# pendant.net
KiCad netlist of a schematic drawn in EAGLE
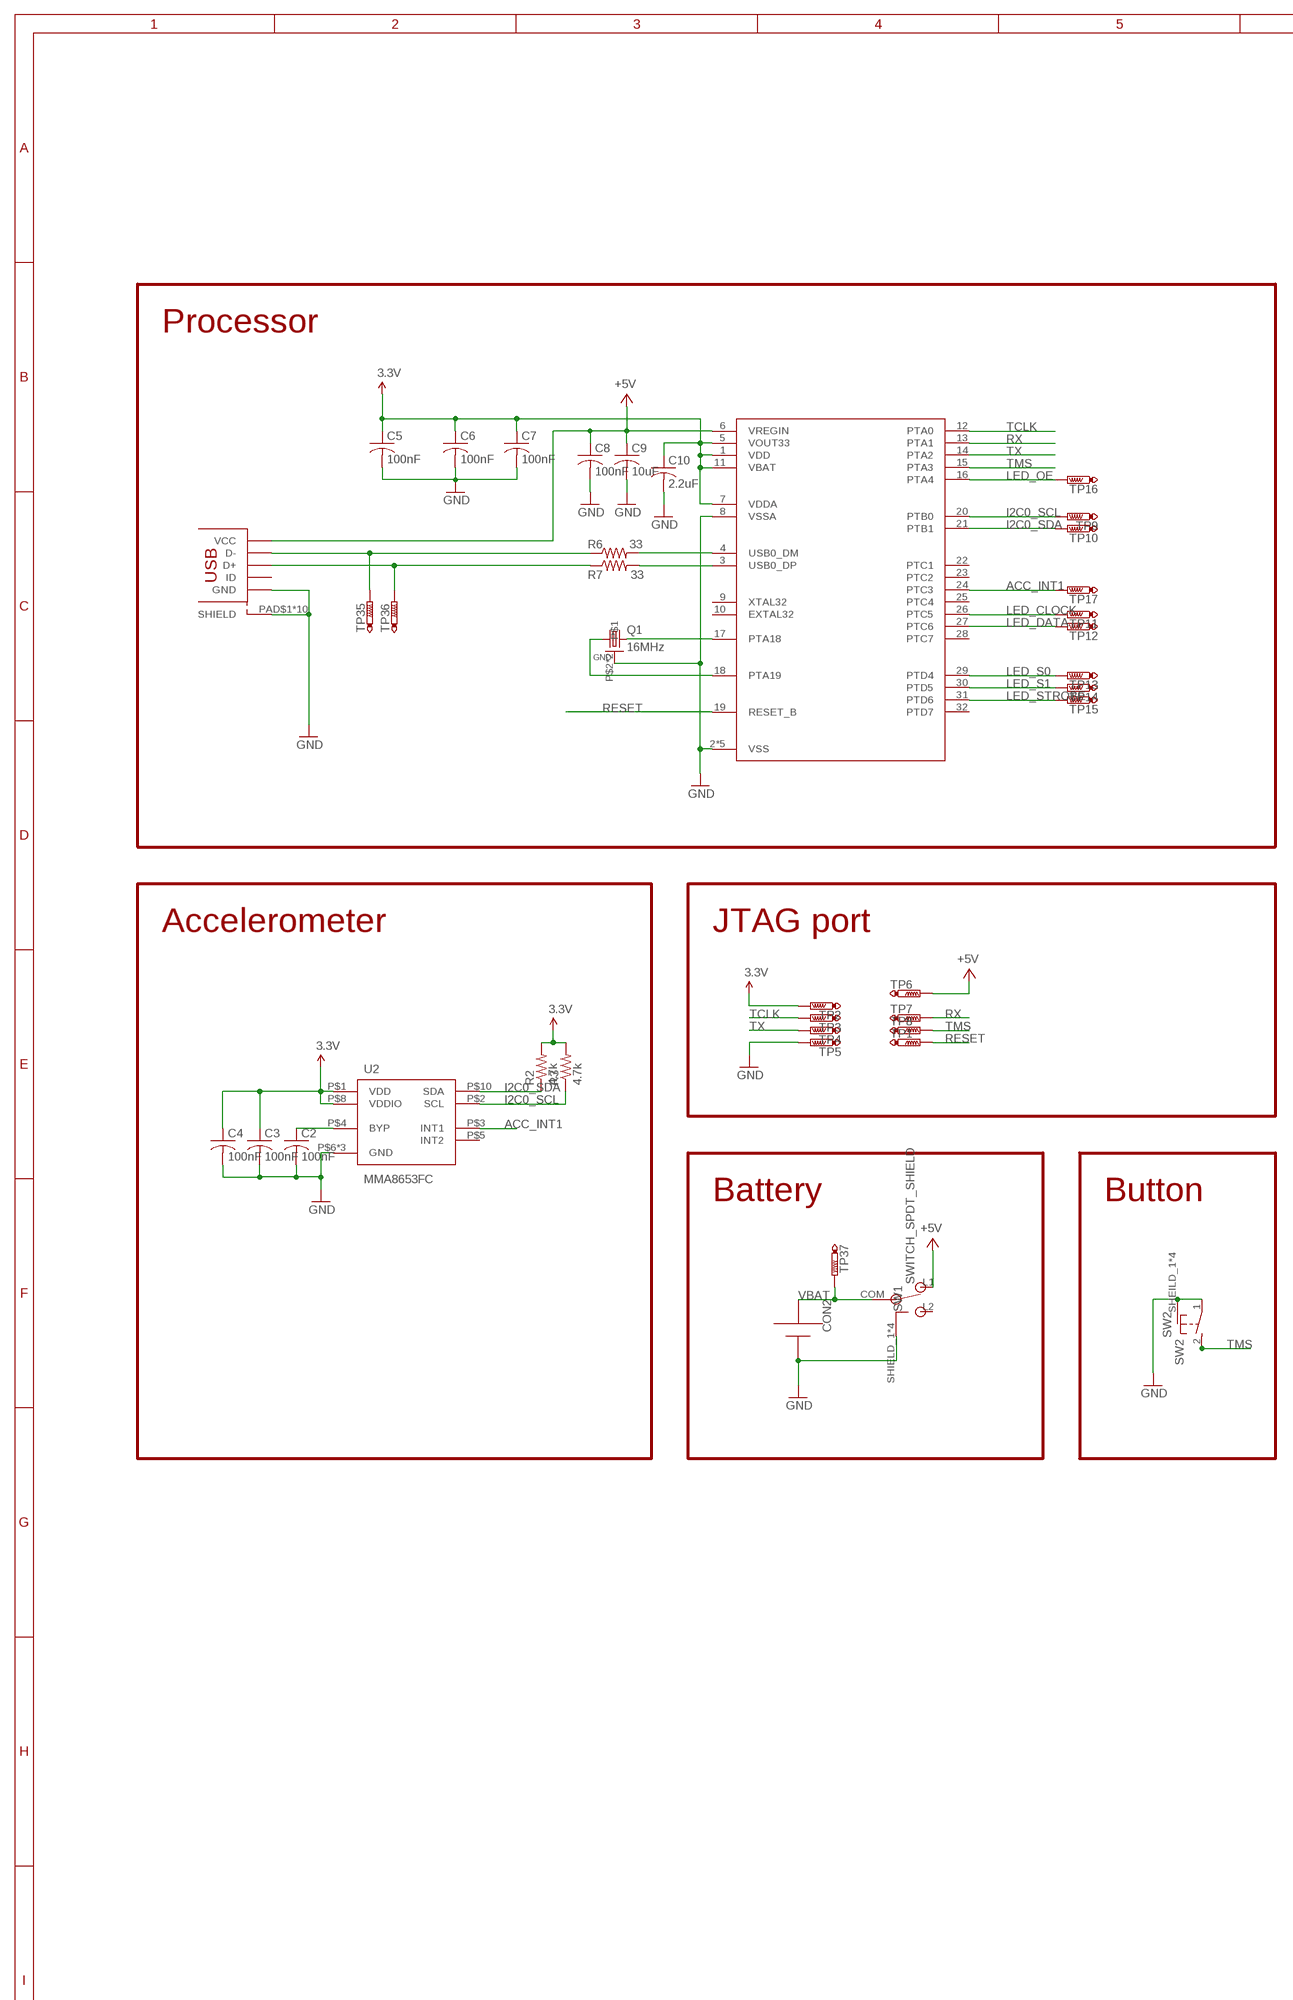
[diagram p0: schematic, sheet 1, part 1 of 2]
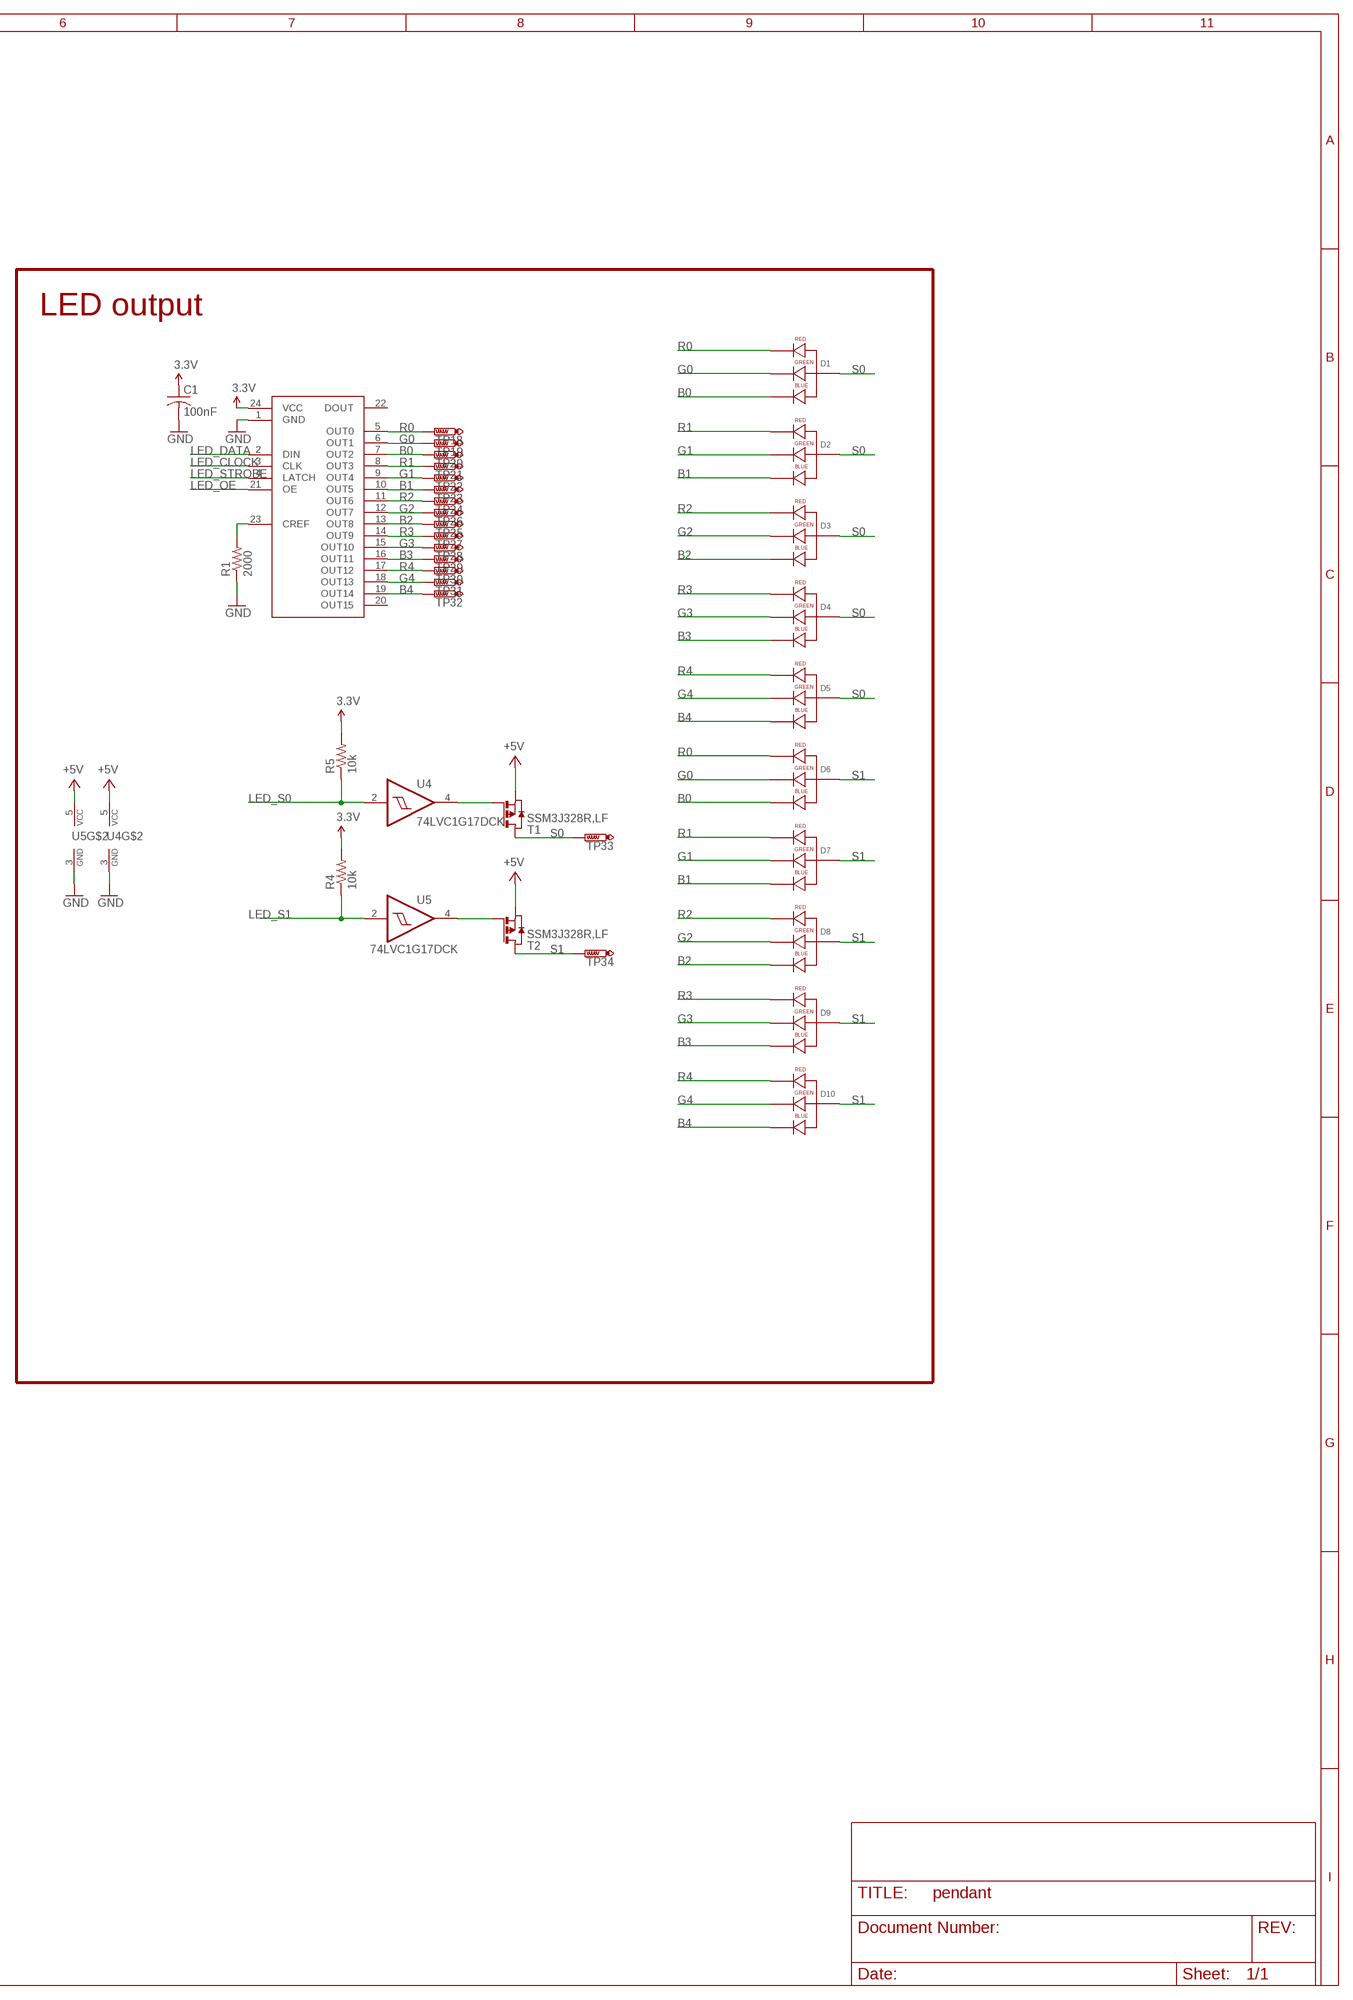
[diagram p1: schematic, sheet 1, part 2 of 2]

(export (version "E")
  (design (tool "Eeschema 10.0.6"))
  (components
    (comp (ref "C1")
      (value "100nF")
      (footprint "eagle-import:C0402")
      (libsource (lib "eagle-import") (part "C-USC0402"))
    )
    (comp (ref "C2")
      (value "100nF")
      (footprint "eagle-import:C0402")
      (libsource (lib "eagle-import") (part "C-USC0402"))
    )
    (comp (ref "C3")
      (value "100nF")
      (footprint "eagle-import:C0402")
      (libsource (lib "eagle-import") (part "C-USC0402"))
    )
    (comp (ref "C4")
      (value "100nF")
      (footprint "eagle-import:C0402")
      (libsource (lib "eagle-import") (part "C-USC0402"))
    )
    (comp (ref "C5")
      (value "100nF")
      (footprint "eagle-import:C0402")
      (libsource (lib "eagle-import") (part "C-USC0402"))
    )
    (comp (ref "C6")
      (value "100nF")
      (footprint "eagle-import:C0402")
      (libsource (lib "eagle-import") (part "C-USC0402"))
    )
    (comp (ref "C7")
      (value "100nF")
      (footprint "eagle-import:C0402")
      (libsource (lib "eagle-import") (part "C-USC0402"))
    )
    (comp (ref "C8")
      (value "100nF")
      (footprint "eagle-import:C0402")
      (libsource (lib "eagle-import") (part "C-USC0402"))
    )
    (comp (ref "C9")
      (value "10uF")
      (footprint "eagle-import:C0603")
      (libsource (lib "eagle-import") (part "C-USC0603"))
    )
    (comp (ref "C10")
      (value "2.2uF")
      (footprint "eagle-import:C0402")
      (libsource (lib "eagle-import") (part "C-USC0402"))
    )
    (comp (ref "CON1")
      (value "USB_MICROSMT+THRUHULE")
      (footprint "eagle-import:USB_MICRO_THRUHOLE")
      (libsource (lib "eagle-import") (part "USB_MICROSMT+THRUHULE"))
    )
    (comp (ref "CON2")
      (value "CR2032X2")
      (footprint "eagle-import:CR2032X2")
      (libsource (lib "eagle-import") (part "CR2032X2"))
    )
    (comp (ref "D1")
      (value "LED-RGB5050")
      (footprint "eagle-import:LED-TRICOLOR-5050-FIXED")
      (libsource (lib "eagle-import") (part "LED-RGB5050"))
    )
    (comp (ref "D2")
      (value "LED-RGB5050")
      (footprint "eagle-import:LED-TRICOLOR-5050-FIXED")
      (libsource (lib "eagle-import") (part "LED-RGB5050"))
    )
    (comp (ref "D3")
      (value "LED-RGB5050")
      (footprint "eagle-import:LED-TRICOLOR-5050-FIXED")
      (libsource (lib "eagle-import") (part "LED-RGB5050"))
    )
    (comp (ref "D4")
      (value "LED-RGB5050")
      (footprint "eagle-import:LED-TRICOLOR-5050-FIXED")
      (libsource (lib "eagle-import") (part "LED-RGB5050"))
    )
    (comp (ref "D5")
      (value "LED-RGB5050")
      (footprint "eagle-import:LED-TRICOLOR-5050-FIXED")
      (libsource (lib "eagle-import") (part "LED-RGB5050"))
    )
    (comp (ref "D6")
      (value "LED-RGB5050")
      (footprint "eagle-import:LED-TRICOLOR-5050-FIXED")
      (libsource (lib "eagle-import") (part "LED-RGB5050"))
    )
    (comp (ref "D7")
      (value "LED-RGB5050")
      (footprint "eagle-import:LED-TRICOLOR-5050-FIXED")
      (libsource (lib "eagle-import") (part "LED-RGB5050"))
    )
    (comp (ref "D8")
      (value "LED-RGB5050")
      (footprint "eagle-import:LED-TRICOLOR-5050-FIXED")
      (libsource (lib "eagle-import") (part "LED-RGB5050"))
    )
    (comp (ref "D9")
      (value "LED-RGB5050")
      (footprint "eagle-import:LED-TRICOLOR-5050-FIXED")
      (libsource (lib "eagle-import") (part "LED-RGB5050"))
    )
    (comp (ref "D10")
      (value "LED-RGB5050")
      (footprint "eagle-import:LED-TRICOLOR-5050-FIXED")
      (libsource (lib "eagle-import") (part "LED-RGB5050"))
    )
    (comp (ref "Q1")
      (value "16MHz")
      (footprint "eagle-import:CRYSTAL_3225")
      (libsource (lib "eagle-import") (part "CRYSTAL_4PAD"))
    )
    (comp (ref "R1")
      (value "2000")
      (footprint "eagle-import:R0402")
      (libsource (lib "eagle-import") (part "R-US_R0402"))
    )
    (comp (ref "R2")
      (value "4.7k")
      (footprint "eagle-import:R0402")
      (libsource (lib "eagle-import") (part "R-US_R0402"))
    )
    (comp (ref "R3")
      (value "4.7k")
      (footprint "eagle-import:R0402")
      (libsource (lib "eagle-import") (part "R-US_R0402"))
    )
    (comp (ref "R4")
      (value "10k")
      (footprint "eagle-import:R0402")
      (libsource (lib "eagle-import") (part "R-US_R0402"))
    )
    (comp (ref "R5")
      (value "10k")
      (footprint "eagle-import:R0402")
      (libsource (lib "eagle-import") (part "R-US_R0402"))
    )
    (comp (ref "R6")
      (value "33")
      (footprint "eagle-import:R0402")
      (libsource (lib "eagle-import") (part "R-US_R0402"))
    )
    (comp (ref "R7")
      (value "33")
      (footprint "eagle-import:R0402")
      (libsource (lib "eagle-import") (part "R-US_R0402"))
    )
    (comp (ref "SW1")
      (value "SWITCH_SPDT_SHIELD")
      (footprint "eagle-import:SWITCH_SMD_90_DEGREE")
      (libsource (lib "eagle-import") (part "SWITCH_SPDT_SHIELD"))
    )
    (comp (ref "SW2")
      (value "SW2")
      (footprint "eagle-import:BUTTON_MOMENTARY_MP5")
      (libsource (lib "eagle-import") (part "BUTTON_MOMENTARY_GROUND"))
    )
    (comp (ref "T1")
      (value "SSM3J328R,LF")
      (footprint "eagle-import:SOT-23")
      (libsource (lib "eagle-import") (part "PMOSSOT23"))
    )
    (comp (ref "T2")
      (value "SSM3J328R,LF")
      (footprint "eagle-import:SOT-23")
      (libsource (lib "eagle-import") (part "PMOSSOT23"))
    )
    (comp (ref "TP1")
      (value "PTR1B1,27")
      (footprint "eagle-import:B1,27")
      (libsource (lib "eagle-import") (part "PTR1B1,27"))
    )
    (comp (ref "TP2")
      (value "PTR1B1,27")
      (footprint "eagle-import:B1,27")
      (libsource (lib "eagle-import") (part "PTR1B1,27"))
    )
    (comp (ref "TP3")
      (value "PTR1B1,27")
      (footprint "eagle-import:B1,27")
      (libsource (lib "eagle-import") (part "PTR1B1,27"))
    )
    (comp (ref "TP4")
      (value "PTR1B1,27")
      (footprint "eagle-import:B1,27")
      (libsource (lib "eagle-import") (part "PTR1B1,27"))
    )
    (comp (ref "TP5")
      (value "PTR1B1,27")
      (footprint "eagle-import:B1,27")
      (libsource (lib "eagle-import") (part "PTR1B1,27"))
    )
    (comp (ref "TP6")
      (value "PTR1B1,27")
      (footprint "eagle-import:B1,27")
      (libsource (lib "eagle-import") (part "PTR1B1,27"))
    )
    (comp (ref "TP7")
      (value "PTR1B1,27")
      (footprint "eagle-import:B1,27")
      (libsource (lib "eagle-import") (part "PTR1B1,27"))
    )
    (comp (ref "TP8")
      (value "PTR1B1,27")
      (footprint "eagle-import:B1,27")
      (libsource (lib "eagle-import") (part "PTR1B1,27"))
    )
    (comp (ref "TP9")
      (value "PTR1B1,27")
      (footprint "eagle-import:B1,27")
      (libsource (lib "eagle-import") (part "PTR1B1,27"))
    )
    (comp (ref "TP10")
      (value "PTR1B1,27")
      (footprint "eagle-import:B1,27")
      (libsource (lib "eagle-import") (part "PTR1B1,27"))
    )
    (comp (ref "TP11")
      (value "PTR1B1,27")
      (footprint "eagle-import:B1,27")
      (libsource (lib "eagle-import") (part "PTR1B1,27"))
    )
    (comp (ref "TP12")
      (value "PTR1B1,27")
      (footprint "eagle-import:B1,27")
      (libsource (lib "eagle-import") (part "PTR1B1,27"))
    )
    (comp (ref "TP13")
      (value "PTR1B1,27")
      (footprint "eagle-import:B1,27")
      (libsource (lib "eagle-import") (part "PTR1B1,27"))
    )
    (comp (ref "TP14")
      (value "PTR1B1,27")
      (footprint "eagle-import:B1,27")
      (libsource (lib "eagle-import") (part "PTR1B1,27"))
    )
    (comp (ref "TP15")
      (value "PTR1B1,27")
      (footprint "eagle-import:B1,27")
      (libsource (lib "eagle-import") (part "PTR1B1,27"))
    )
    (comp (ref "TP16")
      (value "PTR1B1,27")
      (footprint "eagle-import:B1,27")
      (libsource (lib "eagle-import") (part "PTR1B1,27"))
    )
    (comp (ref "TP17")
      (value "PTR1B1,27")
      (footprint "eagle-import:B1,27")
      (libsource (lib "eagle-import") (part "PTR1B1,27"))
    )
    (comp (ref "TP18")
      (value "PTR1B1,27")
      (footprint "eagle-import:B1,27")
      (libsource (lib "eagle-import") (part "PTR1B1,27"))
    )
    (comp (ref "TP19")
      (value "PTR1B1,27")
      (footprint "eagle-import:B1,27")
      (libsource (lib "eagle-import") (part "PTR1B1,27"))
    )
    (comp (ref "TP20")
      (value "PTR1B1,27")
      (footprint "eagle-import:B1,27")
      (libsource (lib "eagle-import") (part "PTR1B1,27"))
    )
    (comp (ref "TP21")
      (value "PTR1B1,27")
      (footprint "eagle-import:B1,27")
      (libsource (lib "eagle-import") (part "PTR1B1,27"))
    )
    (comp (ref "TP22")
      (value "PTR1B1,27")
      (footprint "eagle-import:B1,27")
      (libsource (lib "eagle-import") (part "PTR1B1,27"))
    )
    (comp (ref "TP23")
      (value "PTR1B1,27")
      (footprint "eagle-import:B1,27")
      (libsource (lib "eagle-import") (part "PTR1B1,27"))
    )
    (comp (ref "TP24")
      (value "PTR1B1,27")
      (footprint "eagle-import:B1,27")
      (libsource (lib "eagle-import") (part "PTR1B1,27"))
    )
    (comp (ref "TP25")
      (value "PTR1B1,27")
      (footprint "eagle-import:B1,27")
      (libsource (lib "eagle-import") (part "PTR1B1,27"))
    )
    (comp (ref "TP26")
      (value "PTR1B1,27")
      (footprint "eagle-import:B1,27")
      (libsource (lib "eagle-import") (part "PTR1B1,27"))
    )
    (comp (ref "TP27")
      (value "PTR1B1,27")
      (footprint "eagle-import:B1,27")
      (libsource (lib "eagle-import") (part "PTR1B1,27"))
    )
    (comp (ref "TP28")
      (value "PTR1B1,27")
      (footprint "eagle-import:B1,27")
      (libsource (lib "eagle-import") (part "PTR1B1,27"))
    )
    (comp (ref "TP29")
      (value "PTR1B1,27")
      (footprint "eagle-import:B1,27")
      (libsource (lib "eagle-import") (part "PTR1B1,27"))
    )
    (comp (ref "TP30")
      (value "PTR1B1,27")
      (footprint "eagle-import:B1,27")
      (libsource (lib "eagle-import") (part "PTR1B1,27"))
    )
    (comp (ref "TP31")
      (value "PTR1B1,27")
      (footprint "eagle-import:B1,27")
      (libsource (lib "eagle-import") (part "PTR1B1,27"))
    )
    (comp (ref "TP32")
      (value "PTR1B1,27")
      (footprint "eagle-import:B1,27")
      (libsource (lib "eagle-import") (part "PTR1B1,27"))
    )
    (comp (ref "TP33")
      (value "PTR1B1,27")
      (footprint "eagle-import:B1,27")
      (libsource (lib "eagle-import") (part "PTR1B1,27"))
    )
    (comp (ref "TP34")
      (value "PTR1B1,27")
      (footprint "eagle-import:B1,27")
      (libsource (lib "eagle-import") (part "PTR1B1,27"))
    )
    (comp (ref "TP35")
      (value "PTR1B1,27")
      (footprint "eagle-import:B1,27")
      (libsource (lib "eagle-import") (part "PTR1B1,27"))
    )
    (comp (ref "TP36")
      (value "PTR1B1,27")
      (footprint "eagle-import:B1,27")
      (libsource (lib "eagle-import") (part "PTR1B1,27"))
    )
    (comp (ref "TP37")
      (value "PTR1B1,27")
      (footprint "eagle-import:B1,27")
      (libsource (lib "eagle-import") (part "PTR1B1,27"))
    )
    (comp (ref "U1")
      (value "MK20D--VFM5")
      (footprint "eagle-import:QFN32_5X5_LONGLEADS")
      (libsource (lib "eagle-import") (part "MK20D--VFM5"))
    )
    (comp (ref "U2")
      (value "MMA8653FC")
      (footprint "eagle-import:VFDFN-10")
      (libsource (lib "eagle-import") (part "MMA8653FC"))
    )
    (comp (ref "U3")
      (value "ICN2026DF")
      (footprint "eagle-import:SMD-24-1MM")
      (libsource (lib "eagle-import") (part "ICN2026DF"))
    )
    (comp (ref "U4")
      (value "74LVC1G17DCK")
      (footprint "eagle-import:SC70-5")
      (libsource (lib "eagle-import") (part "741G17DCKLVC"))
    )
    (comp (ref "U5")
      (value "74LVC1G17DCK")
      (footprint "eagle-import:SC70-5")
      (libsource (lib "eagle-import") (part "741G17DCKLVC"))
    )
  )
  (nets
    (net (code "1") (name "+5V") (class "Default")
      (node (ref "C8") (pin "1") (pinfunction "1_1") (pintype "passive"))
      (node (ref "C9") (pin "1") (pinfunction "1_1") (pintype "passive"))
      (node (ref "CON1") (pin "PIN$1") (pinfunction "VCC_PIN$1") (pintype "bidirectional"))
      (node (ref "SW1") (pin "L1") (pinfunction "L1_L1") (pintype "passive"))
      (node (ref "T1") (pin "2") (pinfunction "S_2") (pintype "passive"))
      (node (ref "T2") (pin "2") (pinfunction "S_2") (pintype "passive"))
      (node (ref "TP6") (pin "TP") (pinfunction "TP_TP") (pintype "input"))
      (node (ref "U1") (pin "6") (pinfunction "VREGIN_6") (pintype "bidirectional"))
      (node (ref "U4") (pin "5") (pinfunction "VCC_5") (pintype "power_in"))
      (node (ref "U5") (pin "5") (pinfunction "VCC_5") (pintype "power_in"))
    )
    (net (code "2") (name "/ACC_INT1") (class "Default")
      (node (ref "TP17") (pin "TP") (pinfunction "TP_TP") (pintype "input"))
      (node (ref "U1") (pin "24") (pinfunction "PTC3_24") (pintype "bidirectional"))
      (node (ref "U2") (pin "P$3") (pinfunction "INT1_P$3") (pintype "bidirectional"))
    )
    (net (code "3") (name "/B0") (class "Default")
      (node (ref "D1") (pin "1") (pinfunction "BLUE_CATHODE_1") (pintype "bidirectional"))
      (node (ref "D6") (pin "1") (pinfunction "BLUE_CATHODE_1") (pintype "bidirectional"))
      (node (ref "TP20") (pin "TP") (pinfunction "TP_TP") (pintype "input"))
      (node (ref "U3") (pin "7") (pinfunction "OUT2_7") (pintype "bidirectional"))
    )
    (net (code "4") (name "/B1") (class "Default")
      (node (ref "D2") (pin "1") (pinfunction "BLUE_CATHODE_1") (pintype "bidirectional"))
      (node (ref "D7") (pin "1") (pinfunction "BLUE_CATHODE_1") (pintype "bidirectional"))
      (node (ref "TP23") (pin "TP") (pinfunction "TP_TP") (pintype "input"))
      (node (ref "U3") (pin "10") (pinfunction "OUT5_10") (pintype "bidirectional"))
    )
    (net (code "5") (name "/B2") (class "Default")
      (node (ref "D3") (pin "1") (pinfunction "BLUE_CATHODE_1") (pintype "bidirectional"))
      (node (ref "D8") (pin "1") (pinfunction "BLUE_CATHODE_1") (pintype "bidirectional"))
      (node (ref "TP25") (pin "TP") (pinfunction "TP_TP") (pintype "input"))
      (node (ref "U3") (pin "13") (pinfunction "OUT8_13") (pintype "bidirectional"))
    )
    (net (code "6") (name "/B3") (class "Default")
      (node (ref "D4") (pin "1") (pinfunction "BLUE_CATHODE_1") (pintype "bidirectional"))
      (node (ref "D9") (pin "1") (pinfunction "BLUE_CATHODE_1") (pintype "bidirectional"))
      (node (ref "TP29") (pin "TP") (pinfunction "TP_TP") (pintype "input"))
      (node (ref "U3") (pin "16") (pinfunction "OUT11_16") (pintype "bidirectional"))
    )
    (net (code "7") (name "/B4") (class "Default")
      (node (ref "D10") (pin "1") (pinfunction "BLUE_CATHODE_1") (pintype "bidirectional"))
      (node (ref "D5") (pin "1") (pinfunction "BLUE_CATHODE_1") (pintype "bidirectional"))
      (node (ref "TP32") (pin "TP") (pinfunction "TP_TP") (pintype "input"))
      (node (ref "U3") (pin "19") (pinfunction "OUT14_19") (pintype "bidirectional"))
    )
    (net (code "8") (name "/G0") (class "Default")
      (node (ref "D1") (pin "3") (pinfunction "GREEN_CATHODE_3") (pintype "bidirectional"))
      (node (ref "D6") (pin "3") (pinfunction "GREEN_CATHODE_3") (pintype "bidirectional"))
      (node (ref "TP19") (pin "TP") (pinfunction "TP_TP") (pintype "input"))
      (node (ref "U3") (pin "6") (pinfunction "OUT1_6") (pintype "bidirectional"))
    )
    (net (code "9") (name "/G1") (class "Default")
      (node (ref "D2") (pin "3") (pinfunction "GREEN_CATHODE_3") (pintype "bidirectional"))
      (node (ref "D7") (pin "3") (pinfunction "GREEN_CATHODE_3") (pintype "bidirectional"))
      (node (ref "TP22") (pin "TP") (pinfunction "TP_TP") (pintype "input"))
      (node (ref "U3") (pin "9") (pinfunction "OUT4_9") (pintype "bidirectional"))
    )
    (net (code "10") (name "/G2") (class "Default")
      (node (ref "D3") (pin "3") (pinfunction "GREEN_CATHODE_3") (pintype "bidirectional"))
      (node (ref "D8") (pin "3") (pinfunction "GREEN_CATHODE_3") (pintype "bidirectional"))
      (node (ref "TP26") (pin "TP") (pinfunction "TP_TP") (pintype "input"))
      (node (ref "U3") (pin "12") (pinfunction "OUT7_12") (pintype "bidirectional"))
    )
    (net (code "11") (name "/G3") (class "Default")
      (node (ref "D4") (pin "3") (pinfunction "GREEN_CATHODE_3") (pintype "bidirectional"))
      (node (ref "D9") (pin "3") (pinfunction "GREEN_CATHODE_3") (pintype "bidirectional"))
      (node (ref "TP28") (pin "TP") (pinfunction "TP_TP") (pintype "input"))
      (node (ref "U3") (pin "15") (pinfunction "OUT10_15") (pintype "bidirectional"))
    )
    (net (code "12") (name "/G4") (class "Default")
      (node (ref "D10") (pin "3") (pinfunction "GREEN_CATHODE_3") (pintype "bidirectional"))
      (node (ref "D5") (pin "3") (pinfunction "GREEN_CATHODE_3") (pintype "bidirectional"))
      (node (ref "TP31") (pin "TP") (pinfunction "TP_TP") (pintype "input"))
      (node (ref "U3") (pin "18") (pinfunction "OUT13_18") (pintype "bidirectional"))
    )
    (net (code "13") (name "/I2C0_SCL") (class "Default")
      (node (ref "R3") (pin "1") (pinfunction "1_1") (pintype "passive"))
      (node (ref "TP9") (pin "TP") (pinfunction "TP_TP") (pintype "input"))
      (node (ref "U1") (pin "20") (pinfunction "PTB0_20") (pintype "bidirectional"))
      (node (ref "U2") (pin "P$2") (pinfunction "SCL_P$2") (pintype "bidirectional"))
    )
    (net (code "14") (name "/I2C0_SDA") (class "Default")
      (node (ref "R2") (pin "1") (pinfunction "1_1") (pintype "passive"))
      (node (ref "TP10") (pin "TP") (pinfunction "TP_TP") (pintype "input"))
      (node (ref "U1") (pin "21") (pinfunction "PTB1_21") (pintype "bidirectional"))
      (node (ref "U2") (pin "P$10") (pinfunction "SDA_P$10") (pintype "bidirectional"))
    )
    (net (code "15") (name "/LED_CLOCK") (class "Default")
      (node (ref "TP11") (pin "TP") (pinfunction "TP_TP") (pintype "input"))
      (node (ref "U1") (pin "26") (pinfunction "PTC5_26") (pintype "bidirectional"))
      (node (ref "U3") (pin "3") (pinfunction "CLK_3") (pintype "bidirectional"))
    )
    (net (code "16") (name "/LED_DATA") (class "Default")
      (node (ref "TP12") (pin "TP") (pinfunction "TP_TP") (pintype "input"))
      (node (ref "U1") (pin "27") (pinfunction "PTC6_27") (pintype "bidirectional"))
      (node (ref "U3") (pin "2") (pinfunction "DIN_2") (pintype "bidirectional"))
    )
    (net (code "17") (name "/LED_OE") (class "Default")
      (node (ref "TP16") (pin "TP") (pinfunction "TP_TP") (pintype "input"))
      (node (ref "U1") (pin "16") (pinfunction "PTA4_16") (pintype "bidirectional"))
      (node (ref "U3") (pin "21") (pinfunction "OE_21") (pintype "bidirectional"))
    )
    (net (code "18") (name "/LED_S0") (class "Default")
      (node (ref "R5") (pin "1") (pinfunction "1_1") (pintype "passive"))
      (node (ref "TP13") (pin "TP") (pinfunction "TP_TP") (pintype "input"))
      (node (ref "U1") (pin "29") (pinfunction "PTD4_29") (pintype "bidirectional"))
      (node (ref "U4") (pin "2") (pinfunction "I_2") (pintype "input"))
    )
    (net (code "19") (name "/LED_S1") (class "Default")
      (node (ref "R4") (pin "1") (pinfunction "1_1") (pintype "passive"))
      (node (ref "TP14") (pin "TP") (pinfunction "TP_TP") (pintype "input"))
      (node (ref "U1") (pin "30") (pinfunction "PTD5_30") (pintype "bidirectional"))
      (node (ref "U5") (pin "2") (pinfunction "I_2") (pintype "input"))
    )
    (net (code "20") (name "/LED_STROBE") (class "Default")
      (node (ref "TP15") (pin "TP") (pinfunction "TP_TP") (pintype "input"))
      (node (ref "U1") (pin "31") (pinfunction "PTD6_31") (pintype "bidirectional"))
      (node (ref "U3") (pin "4") (pinfunction "LATCH_4") (pintype "bidirectional"))
    )
    (net (code "21") (name "/R0") (class "Default")
      (node (ref "D1") (pin "2") (pinfunction "RED_CATHODE_2") (pintype "bidirectional"))
      (node (ref "D6") (pin "2") (pinfunction "RED_CATHODE_2") (pintype "bidirectional"))
      (node (ref "TP18") (pin "TP") (pinfunction "TP_TP") (pintype "input"))
      (node (ref "U3") (pin "5") (pinfunction "OUT0_5") (pintype "bidirectional"))
    )
    (net (code "22") (name "/R1") (class "Default")
      (node (ref "D2") (pin "2") (pinfunction "RED_CATHODE_2") (pintype "bidirectional"))
      (node (ref "D7") (pin "2") (pinfunction "RED_CATHODE_2") (pintype "bidirectional"))
      (node (ref "TP21") (pin "TP") (pinfunction "TP_TP") (pintype "input"))
      (node (ref "U3") (pin "8") (pinfunction "OUT3_8") (pintype "bidirectional"))
    )
    (net (code "23") (name "/R2") (class "Default")
      (node (ref "D3") (pin "2") (pinfunction "RED_CATHODE_2") (pintype "bidirectional"))
      (node (ref "D8") (pin "2") (pinfunction "RED_CATHODE_2") (pintype "bidirectional"))
      (node (ref "TP24") (pin "TP") (pinfunction "TP_TP") (pintype "input"))
      (node (ref "U3") (pin "11") (pinfunction "OUT6_11") (pintype "bidirectional"))
    )
    (net (code "24") (name "/R3") (class "Default")
      (node (ref "D4") (pin "2") (pinfunction "RED_CATHODE_2") (pintype "bidirectional"))
      (node (ref "D9") (pin "2") (pinfunction "RED_CATHODE_2") (pintype "bidirectional"))
      (node (ref "TP27") (pin "TP") (pinfunction "TP_TP") (pintype "input"))
      (node (ref "U3") (pin "14") (pinfunction "OUT9_14") (pintype "bidirectional"))
    )
    (net (code "25") (name "/R4") (class "Default")
      (node (ref "D10") (pin "2") (pinfunction "RED_CATHODE_2") (pintype "bidirectional"))
      (node (ref "D5") (pin "2") (pinfunction "RED_CATHODE_2") (pintype "bidirectional"))
      (node (ref "TP30") (pin "TP") (pinfunction "TP_TP") (pintype "input"))
      (node (ref "U3") (pin "17") (pinfunction "OUT12_17") (pintype "bidirectional"))
    )
    (net (code "26") (name "/RESET") (class "Default")
      (node (ref "TP1") (pin "TP") (pinfunction "TP_TP") (pintype "input"))
      (node (ref "U1") (pin "19") (pinfunction "RESET_B_19") (pintype "bidirectional"))
    )
    (net (code "27") (name "/RX") (class "Default")
      (node (ref "TP7") (pin "TP") (pinfunction "TP_TP") (pintype "input"))
      (node (ref "U1") (pin "13") (pinfunction "PTA1_13") (pintype "bidirectional"))
    )
    (net (code "28") (name "/S0") (class "Default")
      (node (ref "D1") (pin "4") (pinfunction "ANODE_4") (pintype "bidirectional"))
      (node (ref "D1") (pin "5") (pinfunction "ANODE_5") (pintype "bidirectional"))
      (node (ref "D1") (pin "6") (pinfunction "ANODE_6") (pintype "bidirectional"))
      (node (ref "D2") (pin "4") (pinfunction "ANODE_4") (pintype "bidirectional"))
      (node (ref "D2") (pin "5") (pinfunction "ANODE_5") (pintype "bidirectional"))
      (node (ref "D2") (pin "6") (pinfunction "ANODE_6") (pintype "bidirectional"))
      (node (ref "D3") (pin "4") (pinfunction "ANODE_4") (pintype "bidirectional"))
      (node (ref "D3") (pin "5") (pinfunction "ANODE_5") (pintype "bidirectional"))
      (node (ref "D3") (pin "6") (pinfunction "ANODE_6") (pintype "bidirectional"))
      (node (ref "D4") (pin "4") (pinfunction "ANODE_4") (pintype "bidirectional"))
      (node (ref "D4") (pin "5") (pinfunction "ANODE_5") (pintype "bidirectional"))
      (node (ref "D4") (pin "6") (pinfunction "ANODE_6") (pintype "bidirectional"))
      (node (ref "D5") (pin "4") (pinfunction "ANODE_4") (pintype "bidirectional"))
      (node (ref "D5") (pin "5") (pinfunction "ANODE_5") (pintype "bidirectional"))
      (node (ref "D5") (pin "6") (pinfunction "ANODE_6") (pintype "bidirectional"))
      (node (ref "T1") (pin "1") (pinfunction "D_1") (pintype "passive"))
      (node (ref "TP33") (pin "TP") (pinfunction "TP_TP") (pintype "input"))
    )
    (net (code "29") (name "/S1") (class "Default")
      (node (ref "D10") (pin "4") (pinfunction "ANODE_4") (pintype "bidirectional"))
      (node (ref "D10") (pin "5") (pinfunction "ANODE_5") (pintype "bidirectional"))
      (node (ref "D10") (pin "6") (pinfunction "ANODE_6") (pintype "bidirectional"))
      (node (ref "D6") (pin "4") (pinfunction "ANODE_4") (pintype "bidirectional"))
      (node (ref "D6") (pin "5") (pinfunction "ANODE_5") (pintype "bidirectional"))
      (node (ref "D6") (pin "6") (pinfunction "ANODE_6") (pintype "bidirectional"))
      (node (ref "D7") (pin "4") (pinfunction "ANODE_4") (pintype "bidirectional"))
      (node (ref "D7") (pin "5") (pinfunction "ANODE_5") (pintype "bidirectional"))
      (node (ref "D7") (pin "6") (pinfunction "ANODE_6") (pintype "bidirectional"))
      (node (ref "D8") (pin "4") (pinfunction "ANODE_4") (pintype "bidirectional"))
      (node (ref "D8") (pin "5") (pinfunction "ANODE_5") (pintype "bidirectional"))
      (node (ref "D8") (pin "6") (pinfunction "ANODE_6") (pintype "bidirectional"))
      (node (ref "D9") (pin "4") (pinfunction "ANODE_4") (pintype "bidirectional"))
      (node (ref "D9") (pin "5") (pinfunction "ANODE_5") (pintype "bidirectional"))
      (node (ref "D9") (pin "6") (pinfunction "ANODE_6") (pintype "bidirectional"))
      (node (ref "T2") (pin "1") (pinfunction "D_1") (pintype "passive"))
      (node (ref "TP34") (pin "TP") (pinfunction "TP_TP") (pintype "input"))
    )
    (net (code "30") (name "/TCLK") (class "Default")
      (node (ref "TP3") (pin "TP") (pinfunction "TP_TP") (pintype "input"))
      (node (ref "U1") (pin "12") (pinfunction "PTA0_12") (pintype "bidirectional"))
    )
    (net (code "31") (name "/TMS") (class "Default")
      (node (ref "SW2") (pin "2") (pinfunction "S_2") (pintype "passive"))
      (node (ref "TP8") (pin "TP") (pinfunction "TP_TP") (pintype "input"))
      (node (ref "U1") (pin "15") (pinfunction "PTA3_15") (pintype "bidirectional"))
    )
    (net (code "32") (name "/TX") (class "Default")
      (node (ref "TP4") (pin "TP") (pinfunction "TP_TP") (pintype "input"))
      (node (ref "U1") (pin "14") (pinfunction "PTA2_14") (pintype "bidirectional"))
    )
    (net (code "33") (name "/VBAT") (class "Default")
      (node (ref "CON2") (pin "+") (pinfunction "+_+") (pintype "bidirectional"))
      (node (ref "SW1") (pin "COM") (pinfunction "COM_COM") (pintype "passive"))
      (node (ref "TP37") (pin "TP") (pinfunction "TP_TP") (pintype "input"))
    )
    (net (code "34") (name "3.3V") (class "Default")
      (node (ref "C1") (pin "1") (pinfunction "1_1") (pintype "passive"))
      (node (ref "C10") (pin "1") (pinfunction "1_1") (pintype "passive"))
      (node (ref "C3") (pin "1") (pinfunction "1_1") (pintype "passive"))
      (node (ref "C4") (pin "1") (pinfunction "1_1") (pintype "passive"))
      (node (ref "C5") (pin "1") (pinfunction "1_1") (pintype "passive"))
      (node (ref "C6") (pin "1") (pinfunction "1_1") (pintype "passive"))
      (node (ref "C7") (pin "1") (pinfunction "1_1") (pintype "passive"))
      (node (ref "R2") (pin "2") (pinfunction "2_2") (pintype "passive"))
      (node (ref "R3") (pin "2") (pinfunction "2_2") (pintype "passive"))
      (node (ref "R4") (pin "2") (pinfunction "2_2") (pintype "passive"))
      (node (ref "R5") (pin "2") (pinfunction "2_2") (pintype "passive"))
      (node (ref "TP2") (pin "TP") (pinfunction "TP_TP") (pintype "input"))
      (node (ref "U1") (pin "1") (pinfunction "VDD_1") (pintype "bidirectional"))
      (node (ref "U1") (pin "11") (pinfunction "VBAT_11") (pintype "bidirectional"))
      (node (ref "U1") (pin "5") (pinfunction "VOUT33_5") (pintype "bidirectional"))
      (node (ref "U1") (pin "7") (pinfunction "VDDA_7") (pintype "bidirectional"))
      (node (ref "U2") (pin "P$1") (pinfunction "VDD_P$1") (pintype "bidirectional"))
      (node (ref "U2") (pin "P$8") (pinfunction "VDDIO_P$8") (pintype "bidirectional"))
      (node (ref "U3") (pin "24") (pinfunction "VCC_24") (pintype "bidirectional"))
    )
    (net (code "35") (name "GND") (class "Default")
      (node (ref "C1") (pin "2") (pinfunction "2_2") (pintype "passive"))
      (node (ref "C10") (pin "2") (pinfunction "2_2") (pintype "passive"))
      (node (ref "C2") (pin "2") (pinfunction "2_2") (pintype "passive"))
      (node (ref "C3") (pin "2") (pinfunction "2_2") (pintype "passive"))
      (node (ref "C4") (pin "2") (pinfunction "2_2") (pintype "passive"))
      (node (ref "C5") (pin "2") (pinfunction "2_2") (pintype "passive"))
      (node (ref "C6") (pin "2") (pinfunction "2_2") (pintype "passive"))
      (node (ref "C7") (pin "2") (pinfunction "2_2") (pintype "passive"))
      (node (ref "C8") (pin "2") (pinfunction "2_2") (pintype "passive"))
      (node (ref "C9") (pin "2") (pinfunction "2_2") (pintype "passive"))
      (node (ref "CON1") (pin "PAD$1") (pinfunction "SHIELD_PAD$1") (pintype "bidirectional"))
      (node (ref "CON1") (pin "PAD$10") (pinfunction "SHIELD_PAD$10") (pintype "bidirectional"))
      (node (ref "CON1") (pin "PAD$2") (pinfunction "SHIELD_PAD$2") (pintype "bidirectional"))
      (node (ref "CON1") (pin "PAD$3") (pinfunction "SHIELD_PAD$3") (pintype "bidirectional"))
      (node (ref "CON1") (pin "PAD$4") (pinfunction "SHIELD_PAD$4") (pintype "bidirectional"))
      (node (ref "CON1") (pin "PAD$5") (pinfunction "SHIELD_PAD$5") (pintype "bidirectional"))
      (node (ref "CON1") (pin "PAD$6") (pinfunction "SHIELD_PAD$6") (pintype "bidirectional"))
      (node (ref "CON1") (pin "PAD$7") (pinfunction "SHIELD_PAD$7") (pintype "bidirectional"))
      (node (ref "CON1") (pin "PAD$8") (pinfunction "SHIELD_PAD$8") (pintype "bidirectional"))
      (node (ref "CON1") (pin "PAD$9") (pinfunction "SHIELD_PAD$9") (pintype "bidirectional"))
      (node (ref "CON1") (pin "PIN$5") (pinfunction "GND_PIN$5") (pintype "bidirectional"))
      (node (ref "CON2") (pin "-") (pinfunction "-_-") (pintype "bidirectional"))
      (node (ref "Q1") (pin "P$2") (pinfunction "P$1_P$2") (pintype "bidirectional"))
      (node (ref "Q1") (pin "P$4") (pinfunction "P$1_P$4") (pintype "bidirectional"))
      (node (ref "R1") (pin "1") (pinfunction "1_1") (pintype "passive"))
      (node (ref "SW1") (pin "SHIELD_1") (pinfunction "SHIELD_SHIELD_1") (pintype "passive"))
      (node (ref "SW1") (pin "SHIELD_2") (pinfunction "SHIELD_SHIELD_2") (pintype "passive"))
      (node (ref "SW1") (pin "SHIELD_3") (pinfunction "SHIELD_SHIELD_3") (pintype "passive"))
      (node (ref "SW1") (pin "SHIELD_4") (pinfunction "SHIELD_SHIELD_4") (pintype "passive"))
      (node (ref "SW2") (pin "1") (pinfunction "P_1") (pintype "passive"))
      (node (ref "SW2") (pin "SHEILD_1") (pinfunction "SHIELD_SHEILD_1") (pintype "passive"))
      (node (ref "SW2") (pin "SHEILD_2") (pinfunction "SHIELD_SHEILD_2") (pintype "passive"))
      (node (ref "SW2") (pin "SHEILD_3") (pinfunction "SHIELD_SHEILD_3") (pintype "passive"))
      (node (ref "SW2") (pin "SHEILD_4") (pinfunction "SHIELD_SHEILD_4") (pintype "passive"))
      (node (ref "TP5") (pin "TP") (pinfunction "TP_TP") (pintype "input"))
      (node (ref "U1") (pin "2") (pinfunction "VSS_2") (pintype "bidirectional"))
      (node (ref "U1") (pin "8") (pinfunction "VSSA_8") (pintype "bidirectional"))
      (node (ref "U1") (pin "PAD@1") (pinfunction "VSS_PAD@1") (pintype "bidirectional"))
      (node (ref "U1") (pin "PAD@11") (pinfunction "VSS_PAD@11") (pintype "bidirectional"))
      (node (ref "U1") (pin "PAD@4") (pinfunction "VSS_PAD@4") (pintype "bidirectional"))
      (node (ref "U1") (pin "PAD@9") (pinfunction "VSS_PAD@9") (pintype "bidirectional"))
      (node (ref "U2") (pin "P$6") (pinfunction "GND_P$6") (pintype "bidirectional"))
      (node (ref "U2") (pin "P$7") (pinfunction "GND_P$7") (pintype "bidirectional"))
      (node (ref "U2") (pin "P$9") (pinfunction "GND_P$9") (pintype "bidirectional"))
      (node (ref "U3") (pin "1") (pinfunction "GND_1") (pintype "bidirectional"))
      (node (ref "U4") (pin "3") (pinfunction "GND_3") (pintype "power_in"))
      (node (ref "U5") (pin "3") (pinfunction "GND_3") (pintype "power_in"))
    )
    (net (code "36") (name "Net-(CON1-D+)") (class "Default")
      (node (ref "CON1") (pin "PIN$3") (pinfunction "D+_PIN$3") (pintype "bidirectional"))
      (node (ref "R7") (pin "1") (pinfunction "1_1") (pintype "passive"))
      (node (ref "TP36") (pin "TP") (pinfunction "TP_TP") (pintype "input"))
    )
    (net (code "37") (name "Net-(CON1-D-)") (class "Default")
      (node (ref "CON1") (pin "PIN$2") (pinfunction "D-_PIN$2") (pintype "bidirectional"))
      (node (ref "R6") (pin "1") (pinfunction "1_1") (pintype "passive"))
      (node (ref "TP35") (pin "TP") (pinfunction "TP_TP") (pintype "input"))
    )
    (net (code "38") (name "Net-(Q1-1)") (class "Default")
      (node (ref "Q1") (pin "P$1") (pinfunction "1_P$1") (pintype "passive"))
      (node (ref "U1") (pin "18") (pinfunction "PTA19_18") (pintype "bidirectional"))
    )
    (net (code "39") (name "Net-(Q1-2)") (class "Default")
      (node (ref "Q1") (pin "P$3") (pinfunction "2_P$3") (pintype "passive"))
      (node (ref "U1") (pin "17") (pinfunction "PTA18_17") (pintype "bidirectional"))
    )
    (net (code "40") (name "Net-(T1-G)") (class "Default")
      (node (ref "T1") (pin "3") (pinfunction "G_3") (pintype "passive"))
      (node (ref "U4") (pin "4") (pinfunction "O_4") (pintype "output"))
    )
    (net (code "41") (name "Net-(T2-G)") (class "Default")
      (node (ref "T2") (pin "3") (pinfunction "G_3") (pintype "passive"))
      (node (ref "U5") (pin "4") (pinfunction "O_4") (pintype "output"))
    )
    (net (code "42") (name "Net-(U1-USB0_DM)") (class "Default")
      (node (ref "R6") (pin "2") (pinfunction "2_2") (pintype "passive"))
      (node (ref "U1") (pin "4") (pinfunction "USB0_DM_4") (pintype "bidirectional"))
    )
    (net (code "43") (name "Net-(U1-USB0_DP)") (class "Default")
      (node (ref "R7") (pin "2") (pinfunction "2_2") (pintype "passive"))
      (node (ref "U1") (pin "3") (pinfunction "USB0_DP_3") (pintype "bidirectional"))
    )
    (net (code "44") (name "Net-(U2-BYP)") (class "Default")
      (node (ref "C2") (pin "1") (pinfunction "1_1") (pintype "passive"))
      (node (ref "U2") (pin "P$4") (pinfunction "BYP_P$4") (pintype "bidirectional"))
    )
    (net (code "45") (name "Net-(U3-CREF)") (class "Default")
      (node (ref "R1") (pin "2") (pinfunction "2_2") (pintype "passive"))
      (node (ref "U3") (pin "23") (pinfunction "CREF_23") (pintype "bidirectional"))
    )
    (net (code "46") (name "unconnected-(CON1-ID-PadPIN$4)") (class "Default")
      (node (ref "CON1") (pin "PIN$4") (pinfunction "ID_PIN$4") (pintype "bidirectional"))
    )
    (net (code "47") (name "unconnected-(SW1-PadL2)") (class "Default")
      (node (ref "SW1") (pin "L2") (pinfunction "L2_L2") (pintype "passive"))
    )
    (net (code "48") (name "unconnected-(U1-EXTAL32-Pad10)") (class "Default")
      (node (ref "U1") (pin "10") (pinfunction "EXTAL32_10") (pintype "bidirectional"))
    )
    (net (code "49") (name "unconnected-(U1-PTC1-Pad22)") (class "Default")
      (node (ref "U1") (pin "22") (pinfunction "PTC1_22") (pintype "bidirectional"))
    )
    (net (code "50") (name "unconnected-(U1-PTC2-Pad23)") (class "Default")
      (node (ref "U1") (pin "23") (pinfunction "PTC2_23") (pintype "bidirectional"))
    )
    (net (code "51") (name "unconnected-(U1-PTC4-Pad25)") (class "Default")
      (node (ref "U1") (pin "25") (pinfunction "PTC4_25") (pintype "bidirectional"))
    )
    (net (code "52") (name "unconnected-(U1-PTC7-Pad28)") (class "Default")
      (node (ref "U1") (pin "28") (pinfunction "PTC7_28") (pintype "bidirectional"))
    )
    (net (code "53") (name "unconnected-(U1-PTD7-Pad32)") (class "Default")
      (node (ref "U1") (pin "32") (pinfunction "PTD7_32") (pintype "bidirectional"))
    )
    (net (code "54") (name "unconnected-(U1-XTAL32-Pad9)") (class "Default")
      (node (ref "U1") (pin "9") (pinfunction "XTAL32_9") (pintype "bidirectional"))
    )
    (net (code "55") (name "unconnected-(U2-INT2-PadP$5)") (class "Default")
      (node (ref "U2") (pin "P$5") (pinfunction "INT2_P$5") (pintype "bidirectional"))
    )
    (net (code "56") (name "unconnected-(U3-DOUT-Pad22)") (class "Default")
      (node (ref "U3") (pin "22") (pinfunction "DOUT_22") (pintype "bidirectional"))
    )
    (net (code "57") (name "unconnected-(U3-OUT15-Pad20)") (class "Default")
      (node (ref "U3") (pin "20") (pinfunction "OUT15_20") (pintype "bidirectional"))
    )
  )
)
